# cutOffMosfetOLD.net
KiCad netlist of a schematic drawn in EAGLE
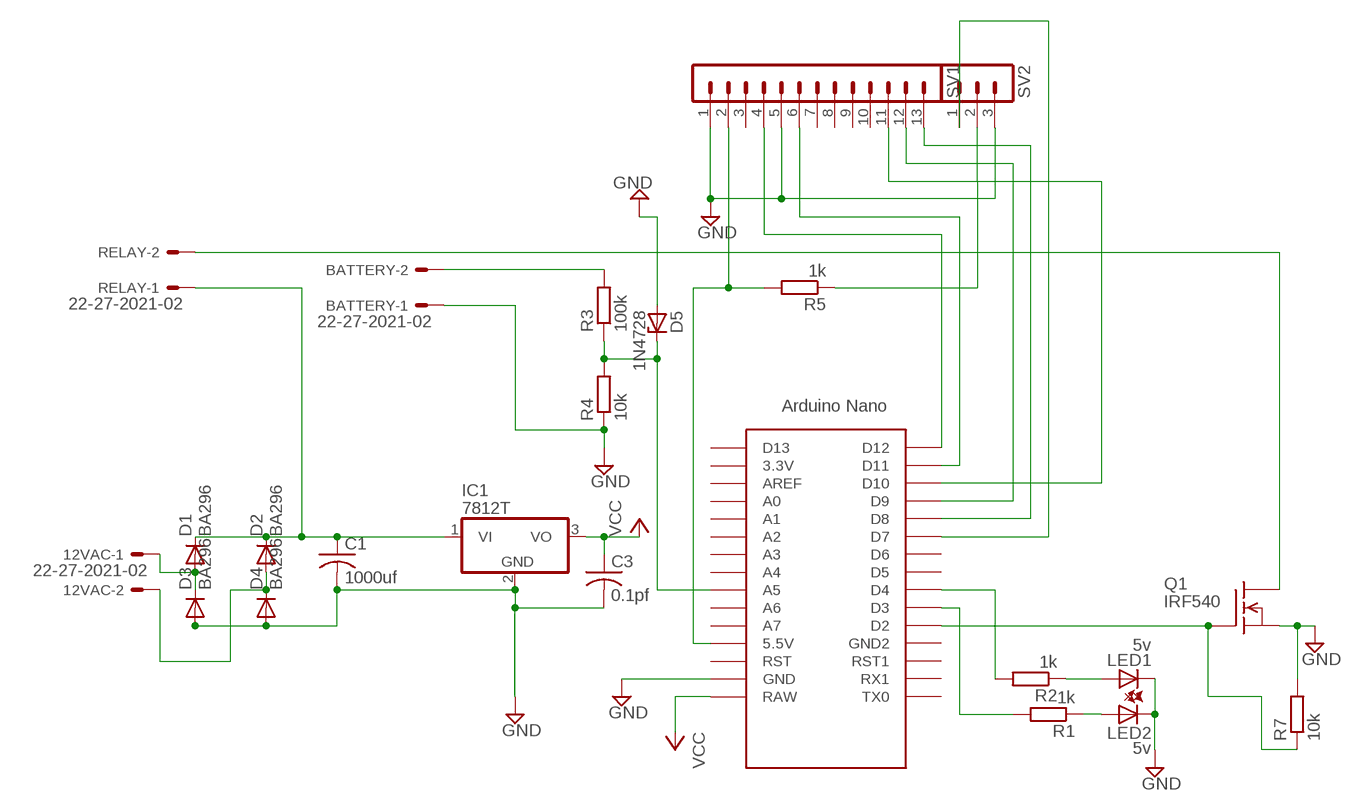
[diagram p0: schematic, sheet 1]

(export (version "E")
  (design (tool "Eeschema 10.0.6"))
  (components
    (comp (ref "12VAC")
      (value "22-27-2021-02")
      (footprint "eagle-import:6410-02")
      (libsource (lib "eagle-import") (part "22-?-0227-2021"))
    )
    (comp (ref "BATTERY")
      (value "22-27-2021-02")
      (footprint "eagle-import:6410-02")
      (libsource (lib "eagle-import") (part "22-?-0227-2021"))
    )
    (comp (ref "C1")
      (value "1000uf")
      (footprint "eagle-import:C050-025X075")
      (libsource (lib "eagle-import") (part "C-US050-025X075"))
    )
    (comp (ref "C3")
      (value "0.1pf")
      (footprint "eagle-import:C050-025X075")
      (libsource (lib "eagle-import") (part "C-US050-025X075"))
    )
    (comp (ref "D1")
      (value "BA296")
      (footprint "eagle-import:P2-15")
      (libsource (lib "eagle-import") (part "BA296"))
    )
    (comp (ref "D2")
      (value "BA296")
      (footprint "eagle-import:P2-15")
      (libsource (lib "eagle-import") (part "BA296"))
    )
    (comp (ref "D3")
      (value "BA296")
      (footprint "eagle-import:P2-15")
      (libsource (lib "eagle-import") (part "BA296"))
    )
    (comp (ref "D4")
      (value "BA296")
      (footprint "eagle-import:P2-15")
      (libsource (lib "eagle-import") (part "BA296"))
    )
    (comp (ref "D5")
      (value "1N4728")
      (footprint "eagle-import:DO41Z10")
      (libsource (lib "eagle-import") (part "1N4728"))
    )
    (comp (ref "IC1")
      (value "7812T")
      (footprint "eagle-import:TO220H")
      (libsource (lib "eagle-import") (part "78T12"))
    )
    (comp (ref "LED1")
      (value "5v")
      (footprint "eagle-import:LED5MM")
      (libsource (lib "eagle-import") (part "LED5MM"))
    )
    (comp (ref "LED2")
      (value "5v")
      (footprint "eagle-import:LED5MM")
      (libsource (lib "eagle-import") (part "LED5MM"))
    )
    (comp (ref "Q1")
      (value "IRF540")
      (footprint "eagle-import:TO220")
      (libsource (lib "eagle-import") (part "IRF540"))
    )
    (comp (ref "R1")
      (value "1k")
      (footprint "eagle-import:0207_10")
      (libsource (lib "eagle-import") (part "R0207/10"))
    )
    (comp (ref "R2")
      (value "1k")
      (footprint "eagle-import:0207_10")
      (libsource (lib "eagle-import") (part "R0207/10"))
    )
    (comp (ref "R3")
      (value "100k")
      (footprint "eagle-import:0207_10")
      (libsource (lib "eagle-import") (part "R0207/10"))
    )
    (comp (ref "R4")
      (value "10k")
      (footprint "eagle-import:0207_10")
      (libsource (lib "eagle-import") (part "R0207/10"))
    )
    (comp (ref "R5")
      (value "1k")
      (footprint "eagle-import:0207_10")
      (libsource (lib "eagle-import") (part "R0207/10"))
    )
    (comp (ref "R7")
      (value "10k")
      (footprint "eagle-import:0207_10")
      (libsource (lib "eagle-import") (part "R0207/10"))
    )
    (comp (ref "RELAY")
      (value "22-27-2021-02")
      (footprint "eagle-import:6410-02")
      (libsource (lib "eagle-import") (part "22-?-0227-2021"))
    )
    (comp (ref "SV1")
      (value "MA13-1")
      (footprint "eagle-import:MA13-1")
      (libsource (lib "eagle-import") (part "MA13-1"))
    )
    (comp (ref "SV2")
      (value "MA03-1")
      (footprint "eagle-import:MA03-1")
      (libsource (lib "eagle-import") (part "MA03-1"))
    )
    (comp (ref "U$1")
      (value "NANO")
      (footprint "eagle-import:NANO")
      (libsource (lib "eagle-import") (part "NANO"))
    )
  )
  (nets
    (net (code "1") (name "GND") (class "Default")
      (node (ref "BATTERY") (pin "1") (pinfunction "S_1") (pintype "passive"))
      (node (ref "C1") (pin "2") (pinfunction "2_2") (pintype "passive"))
      (node (ref "C3") (pin "2") (pinfunction "2_2") (pintype "passive"))
      (node (ref "D3") (pin "A") (pinfunction "A_A") (pintype "passive"))
      (node (ref "D4") (pin "A") (pinfunction "A_A") (pintype "passive"))
      (node (ref "D5") (pin "A") (pinfunction "A_A") (pintype "passive"))
      (node (ref "IC1") (pin "2") (pinfunction "GND_2") (pintype "passive"))
      (node (ref "LED1") (pin "K") (pinfunction "C_K") (pintype "passive"))
      (node (ref "LED2") (pin "K") (pinfunction "C_K") (pintype "passive"))
      (node (ref "Q1") (pin "3") (pinfunction "S_3") (pintype "passive"))
      (node (ref "R4") (pin "1") (pinfunction "1_1") (pintype "passive"))
      (node (ref "R7") (pin "2") (pinfunction "2_2") (pintype "passive"))
      (node (ref "SV1") (pin "1") (pinfunction "1_1") (pintype "passive"))
      (node (ref "SV1") (pin "5") (pinfunction "5_5") (pintype "passive"))
      (node (ref "SV2") (pin "3") (pinfunction "3_3") (pintype "passive"))
      (node (ref "U$1") (pin "GND") (pinfunction "GND_GND") (pintype "bidirectional"))
    )
    (net (code "2") (name "Net-(12VACA-S)") (class "Default")
      (node (ref "12VAC") (pin "1") (pinfunction "S_1") (pintype "passive"))
      (node (ref "D1") (pin "A") (pinfunction "A_A") (pintype "passive"))
      (node (ref "D3") (pin "C") (pinfunction "C_C") (pintype "passive"))
    )
    (net (code "3") (name "Net-(12VACB-S)") (class "Default")
      (node (ref "12VAC") (pin "2") (pinfunction "S_2") (pintype "passive"))
      (node (ref "D2") (pin "A") (pinfunction "A_A") (pintype "passive"))
      (node (ref "D4") (pin "C") (pinfunction "C_C") (pintype "passive"))
    )
    (net (code "4") (name "Net-(BATTERYB-S)") (class "Default")
      (node (ref "BATTERY") (pin "2") (pinfunction "S_2") (pintype "passive"))
      (node (ref "R3") (pin "2") (pinfunction "2_2") (pintype "passive"))
    )
    (net (code "5") (name "Net-(D5-PadC)") (class "Default")
      (node (ref "D5") (pin "C") (pinfunction "C_C") (pintype "passive"))
      (node (ref "R3") (pin "1") (pinfunction "1_1") (pintype "passive"))
      (node (ref "R4") (pin "2") (pinfunction "2_2") (pintype "passive"))
      (node (ref "U$1") (pin "A5") (pinfunction "A5_A5") (pintype "bidirectional"))
    )
    (net (code "6") (name "Net-(IC1-VI)") (class "Default")
      (node (ref "C1") (pin "1") (pinfunction "1_1") (pintype "passive"))
      (node (ref "D1") (pin "C") (pinfunction "C_C") (pintype "passive"))
      (node (ref "D2") (pin "C") (pinfunction "C_C") (pintype "passive"))
      (node (ref "IC1") (pin "1") (pinfunction "VI_1") (pintype "input"))
      (node (ref "RELAY") (pin "1") (pinfunction "S_1") (pintype "passive"))
    )
    (net (code "7") (name "Net-(LED1-PadA)") (class "Default")
      (node (ref "LED1") (pin "A") (pinfunction "A_A") (pintype "passive"))
      (node (ref "R2") (pin "1") (pinfunction "1_1") (pintype "passive"))
    )
    (net (code "8") (name "Net-(LED2-PadA)") (class "Default")
      (node (ref "LED2") (pin "A") (pinfunction "A_A") (pintype "passive"))
      (node (ref "R1") (pin "1") (pinfunction "1_1") (pintype "passive"))
    )
    (net (code "9") (name "Net-(Q1-D)") (class "Default")
      (node (ref "Q1") (pin "2") (pinfunction "D_2") (pintype "passive"))
      (node (ref "RELAY") (pin "2") (pinfunction "S_2") (pintype "passive"))
    )
    (net (code "10") (name "Net-(Q1-G)") (class "Default")
      (node (ref "Q1") (pin "1") (pinfunction "G_1") (pintype "passive"))
      (node (ref "R7") (pin "1") (pinfunction "1_1") (pintype "passive"))
      (node (ref "U$1") (pin "D2") (pinfunction "D2_D2") (pintype "bidirectional"))
    )
    (net (code "11") (name "Net-(R1-Pad2)") (class "Default")
      (node (ref "R1") (pin "2") (pinfunction "2_2") (pintype "passive"))
      (node (ref "U$1") (pin "D3") (pinfunction "D3_D3") (pintype "bidirectional"))
    )
    (net (code "12") (name "Net-(R2-Pad2)") (class "Default")
      (node (ref "R2") (pin "2") (pinfunction "2_2") (pintype "passive"))
      (node (ref "U$1") (pin "D4") (pinfunction "D4_D4") (pintype "bidirectional"))
    )
    (net (code "13") (name "Net-(R5-Pad1)") (class "Default")
      (node (ref "R5") (pin "1") (pinfunction "1_1") (pintype "passive"))
      (node (ref "SV2") (pin "2") (pinfunction "2_2") (pintype "passive"))
    )
    (net (code "14") (name "Net-(SV1-Pad4)") (class "Default")
      (node (ref "SV1") (pin "4") (pinfunction "4_4") (pintype "passive"))
      (node (ref "U$1") (pin "D12") (pinfunction "D12_D12") (pintype "bidirectional"))
    )
    (net (code "15") (name "Net-(SV1-Pad6)") (class "Default")
      (node (ref "SV1") (pin "6") (pinfunction "6_6") (pintype "passive"))
      (node (ref "U$1") (pin "D11") (pinfunction "D11_D11") (pintype "bidirectional"))
    )
    (net (code "16") (name "Net-(SV1-Pad11)") (class "Default")
      (node (ref "SV1") (pin "11") (pinfunction "11_11") (pintype "passive"))
      (node (ref "U$1") (pin "D10") (pinfunction "D10_D10") (pintype "bidirectional"))
    )
    (net (code "17") (name "Net-(SV1-Pad12)") (class "Default")
      (node (ref "SV1") (pin "12") (pinfunction "12_12") (pintype "passive"))
      (node (ref "U$1") (pin "D9") (pinfunction "D9_D9") (pintype "bidirectional"))
    )
    (net (code "18") (name "Net-(SV1-Pad13)") (class "Default")
      (node (ref "SV1") (pin "13") (pinfunction "13_13") (pintype "passive"))
      (node (ref "U$1") (pin "D8") (pinfunction "D8_D8") (pintype "bidirectional"))
    )
    (net (code "19") (name "Net-(SV2-Pad1)") (class "Default")
      (node (ref "SV2") (pin "1") (pinfunction "1_1") (pintype "passive"))
      (node (ref "U$1") (pin "D7") (pinfunction "D7_D7") (pintype "bidirectional"))
    )
    (net (code "20") (name "Net-(U$1-5.5V)") (class "Default")
      (node (ref "R5") (pin "2") (pinfunction "2_2") (pintype "passive"))
      (node (ref "SV1") (pin "2") (pinfunction "2_2") (pintype "passive"))
      (node (ref "U$1") (pin "5V") (pinfunction "5.5V_5V") (pintype "bidirectional"))
    )
    (net (code "21") (name "VCC") (class "Default")
      (node (ref "C3") (pin "1") (pinfunction "1_1") (pintype "passive"))
      (node (ref "IC1") (pin "3") (pinfunction "VO_3") (pintype "passive"))
      (node (ref "U$1") (pin "RAW") (pinfunction "RAW_RAW") (pintype "bidirectional"))
    )
    (net (code "22") (name "unconnected-(SV1-Pad3)") (class "Default")
      (node (ref "SV1") (pin "3") (pinfunction "3_3") (pintype "passive"))
    )
    (net (code "23") (name "unconnected-(SV1-Pad7)") (class "Default")
      (node (ref "SV1") (pin "7") (pinfunction "7_7") (pintype "passive"))
    )
    (net (code "24") (name "unconnected-(SV1-Pad8)") (class "Default")
      (node (ref "SV1") (pin "8") (pinfunction "8_8") (pintype "passive"))
    )
    (net (code "25") (name "unconnected-(SV1-Pad9)") (class "Default")
      (node (ref "SV1") (pin "9") (pinfunction "9_9") (pintype "passive"))
    )
    (net (code "26") (name "unconnected-(SV1-Pad10)") (class "Default")
      (node (ref "SV1") (pin "10") (pinfunction "10_10") (pintype "passive"))
    )
    (net (code "27") (name "unconnected-(U$1-GND2-PadGND1)") (class "Default")
      (node (ref "U$1") (pin "GND1") (pinfunction "GND2_GND1") (pintype "bidirectional"))
    )
    (net (code "28") (name "unconnected-(U$1-Pad3.3V)") (class "Default")
      (node (ref "U$1") (pin "3.3V") (pinfunction "3.3V_3.3V") (pintype "bidirectional"))
    )
    (net (code "29") (name "unconnected-(U$1-PadA0)") (class "Default")
      (node (ref "U$1") (pin "A0") (pinfunction "A0_A0") (pintype "bidirectional"))
    )
    (net (code "30") (name "unconnected-(U$1-PadA1)") (class "Default")
      (node (ref "U$1") (pin "A1") (pinfunction "A1_A1") (pintype "bidirectional"))
    )
    (net (code "31") (name "unconnected-(U$1-PadA2)") (class "Default")
      (node (ref "U$1") (pin "A2") (pinfunction "A2_A2") (pintype "bidirectional"))
    )
    (net (code "32") (name "unconnected-(U$1-PadA3)") (class "Default")
      (node (ref "U$1") (pin "A3") (pinfunction "A3_A3") (pintype "bidirectional"))
    )
    (net (code "33") (name "unconnected-(U$1-PadA4)") (class "Default")
      (node (ref "U$1") (pin "A4") (pinfunction "A4_A4") (pintype "bidirectional"))
    )
    (net (code "34") (name "unconnected-(U$1-PadA6)") (class "Default")
      (node (ref "U$1") (pin "A6") (pinfunction "A6_A6") (pintype "bidirectional"))
    )
    (net (code "35") (name "unconnected-(U$1-PadA7)") (class "Default")
      (node (ref "U$1") (pin "A7") (pinfunction "A7_A7") (pintype "bidirectional"))
    )
    (net (code "36") (name "unconnected-(U$1-PadAREF)") (class "Default")
      (node (ref "U$1") (pin "AREF") (pinfunction "AREF_AREF") (pintype "bidirectional"))
    )
    (net (code "37") (name "unconnected-(U$1-PadD5)") (class "Default")
      (node (ref "U$1") (pin "D5") (pinfunction "D5_D5") (pintype "bidirectional"))
    )
    (net (code "38") (name "unconnected-(U$1-PadD6)") (class "Default")
      (node (ref "U$1") (pin "D6") (pinfunction "D6_D6") (pintype "bidirectional"))
    )
    (net (code "39") (name "unconnected-(U$1-PadD13)") (class "Default")
      (node (ref "U$1") (pin "D13") (pinfunction "D13_D13") (pintype "bidirectional"))
    )
    (net (code "40") (name "unconnected-(U$1-PadICSP1)") (class "Default")
      (node (ref "U$1") (pin "ICSP1") (pinfunction "ICSP1_ICSP1") (pintype "bidirectional"))
    )
    (net (code "41") (name "unconnected-(U$1-PadICSP2)") (class "Default")
      (node (ref "U$1") (pin "ICSP2") (pinfunction "ICSP2_ICSP2") (pintype "bidirectional"))
    )
    (net (code "42") (name "unconnected-(U$1-PadICSP3)") (class "Default")
      (node (ref "U$1") (pin "ICSP3") (pinfunction "ICSP3_ICSP3") (pintype "bidirectional"))
    )
    (net (code "43") (name "unconnected-(U$1-PadICSP4)") (class "Default")
      (node (ref "U$1") (pin "ICSP4") (pinfunction "ICSP4_ICSP4") (pintype "bidirectional"))
    )
    (net (code "44") (name "unconnected-(U$1-PadICSP5)") (class "Default")
      (node (ref "U$1") (pin "ICSP5") (pinfunction "ICSP5_ICSP5") (pintype "bidirectional"))
    )
    (net (code "45") (name "unconnected-(U$1-PadICSP6)") (class "Default")
      (node (ref "U$1") (pin "ICSP6") (pinfunction "ICSP6_ICSP6") (pintype "bidirectional"))
    )
    (net (code "46") (name "unconnected-(U$1-PadRST)") (class "Default")
      (node (ref "U$1") (pin "RST") (pinfunction "RST_RST") (pintype "bidirectional"))
    )
    (net (code "47") (name "unconnected-(U$1-PadRST1)") (class "Default")
      (node (ref "U$1") (pin "RST1") (pinfunction "RST1_RST1") (pintype "bidirectional"))
    )
    (net (code "48") (name "unconnected-(U$1-PadRX1)") (class "Default")
      (node (ref "U$1") (pin "RX1") (pinfunction "RX1_RX1") (pintype "bidirectional"))
    )
    (net (code "49") (name "unconnected-(U$1-PadTX0)") (class "Default")
      (node (ref "U$1") (pin "TX0") (pinfunction "TX0_TX0") (pintype "bidirectional"))
    )
  )
)
